# EEGAmp_Thruhole.net
KiCad netlist of a schematic drawn in EAGLE
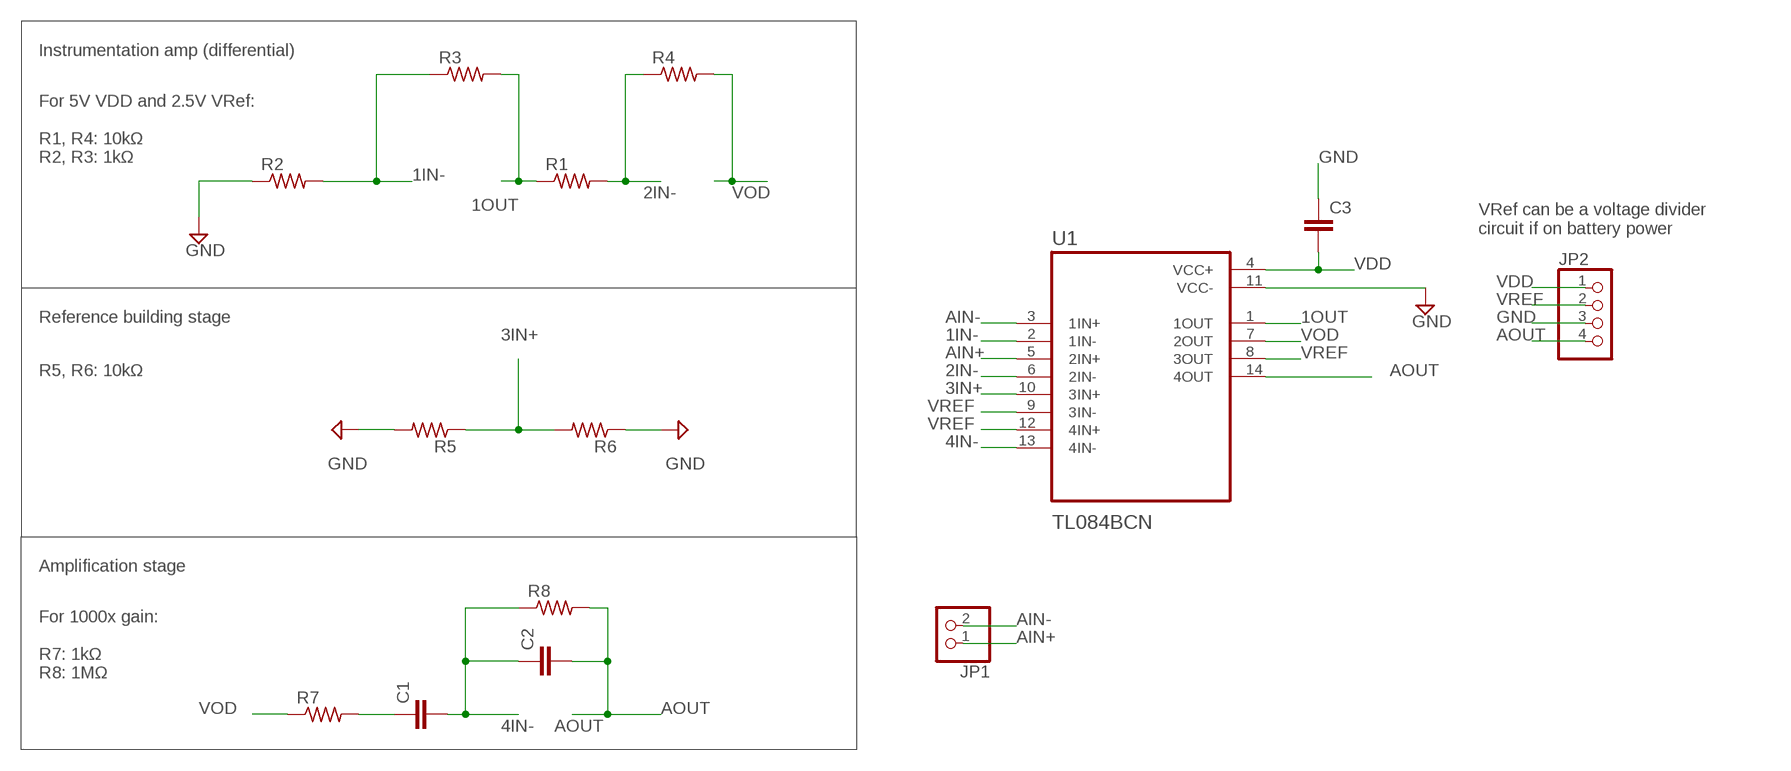
[diagram p0: schematic, sheet 1]

(export (version "E")
  (design (tool "Eeschema 10.0.6"))
  (components
    (comp (ref "C1")
      (value "C2.5/2")
      (footprint "eagle-import:C2.5-2")
      (libsource (lib "eagle-import") (part "C2.5/2"))
    )
    (comp (ref "C2")
      (value "C2.5/2")
      (footprint "eagle-import:C2.5-2")
      (libsource (lib "eagle-import") (part "C2.5/2"))
    )
    (comp (ref "C3")
      (value "C2.5/2")
      (footprint "eagle-import:C2.5-2")
      (libsource (lib "eagle-import") (part "C2.5/2"))
    )
    (comp (ref "JP1")
      (value "PINHD-1X2")
      (footprint "eagle-import:1X02")
      (libsource (lib "eagle-import") (part "PINHD-1X2"))
    )
    (comp (ref "JP2")
      (value "PINHD-1X4")
      (footprint "eagle-import:1X04")
      (libsource (lib "eagle-import") (part "PINHD-1X4"))
    )
    (comp (ref "R1")
      (value "R-US_0204/5")
      (footprint "eagle-import:0204_5")
      (libsource (lib "eagle-import") (part "R-US_0204/5"))
    )
    (comp (ref "R2")
      (value "R-US_0204/5")
      (footprint "eagle-import:0204_5")
      (libsource (lib "eagle-import") (part "R-US_0204/5"))
    )
    (comp (ref "R3")
      (value "R-US_0204/5")
      (footprint "eagle-import:0204_5")
      (libsource (lib "eagle-import") (part "R-US_0204/5"))
    )
    (comp (ref "R4")
      (value "R-US_0204/5")
      (footprint "eagle-import:0204_5")
      (libsource (lib "eagle-import") (part "R-US_0204/5"))
    )
    (comp (ref "R5")
      (value "R-US_0204/5")
      (footprint "eagle-import:0204_5")
      (libsource (lib "eagle-import") (part "R-US_0204/5"))
    )
    (comp (ref "R6")
      (value "R-US_0204/5")
      (footprint "eagle-import:0204_5")
      (libsource (lib "eagle-import") (part "R-US_0204/5"))
    )
    (comp (ref "R7")
      (value "R-US_0204/5")
      (footprint "eagle-import:0204_5")
      (libsource (lib "eagle-import") (part "R-US_0204/5"))
    )
    (comp (ref "R8")
      (value "R-US_0204/5")
      (footprint "eagle-import:0204_5")
      (libsource (lib "eagle-import") (part "R-US_0204/5"))
    )
    (comp (ref "U1")
      (value "TL084BCN")
      (footprint "eagle-import:DIP794W45P254L1969H508Q14")
      (fields (field (name "MF") "Texas Instruments"))
      (libsource (lib "eagle-import") (part "TL084BCN"))
    )
  )
  (nets
    (net (code "1") (name "/1IN-") (class "Default")
      (node (ref "R2") (pin "2") (pinfunction "2_2") (pintype "passive"))
      (node (ref "R3") (pin "1") (pinfunction "1_1") (pintype "passive"))
      (node (ref "U1") (pin "2") (pinfunction "1IN-_2") (pintype "input"))
    )
    (net (code "2") (name "/1OUT") (class "Default")
      (node (ref "R1") (pin "1") (pinfunction "1_1") (pintype "passive"))
      (node (ref "R3") (pin "2") (pinfunction "2_2") (pintype "passive"))
      (node (ref "U1") (pin "1") (pinfunction "1OUT_1") (pintype "output"))
    )
    (net (code "3") (name "/2IN-") (class "Default")
      (node (ref "R1") (pin "2") (pinfunction "2_2") (pintype "passive"))
      (node (ref "R4") (pin "1") (pinfunction "1_1") (pintype "passive"))
      (node (ref "U1") (pin "6") (pinfunction "2IN-_6") (pintype "input"))
    )
    (net (code "4") (name "/3IN+") (class "Default")
      (node (ref "R5") (pin "1") (pinfunction "1_1") (pintype "passive"))
      (node (ref "R6") (pin "2") (pinfunction "2_2") (pintype "passive"))
      (node (ref "U1") (pin "10") (pinfunction "3IN+_10") (pintype "input"))
    )
    (net (code "5") (name "/4IN-") (class "Default")
      (node (ref "C1") (pin "2") (pinfunction "2_2") (pintype "passive"))
      (node (ref "C2") (pin "1") (pinfunction "1_1") (pintype "passive"))
      (node (ref "R8") (pin "1") (pinfunction "1_1") (pintype "passive"))
      (node (ref "U1") (pin "13") (pinfunction "4IN-_13") (pintype "input"))
    )
    (net (code "6") (name "/AIN+") (class "Default")
      (node (ref "JP1") (pin "1") (pinfunction "1_1") (pintype "passive"))
      (node (ref "U1") (pin "5") (pinfunction "2IN+_5") (pintype "input"))
    )
    (net (code "7") (name "/AIN-") (class "Default")
      (node (ref "JP1") (pin "2") (pinfunction "2_2") (pintype "passive"))
      (node (ref "U1") (pin "3") (pinfunction "1IN+_3") (pintype "input"))
    )
    (net (code "8") (name "/AOUT") (class "Default")
      (node (ref "C2") (pin "2") (pinfunction "2_2") (pintype "passive"))
      (node (ref "JP2") (pin "4") (pinfunction "4_4") (pintype "passive"))
      (node (ref "R8") (pin "2") (pinfunction "2_2") (pintype "passive"))
      (node (ref "U1") (pin "14") (pinfunction "4OUT_14") (pintype "output"))
    )
    (net (code "9") (name "/VDD") (class "Default")
      (node (ref "C3") (pin "2") (pinfunction "2_2") (pintype "passive"))
      (node (ref "JP2") (pin "1") (pinfunction "1_1") (pintype "passive"))
      (node (ref "U1") (pin "4") (pinfunction "VCC+_4") (pintype "power_in"))
    )
    (net (code "10") (name "/VOD") (class "Default")
      (node (ref "R4") (pin "2") (pinfunction "2_2") (pintype "passive"))
      (node (ref "R7") (pin "1") (pinfunction "1_1") (pintype "passive"))
      (node (ref "U1") (pin "7") (pinfunction "2OUT_7") (pintype "output"))
    )
    (net (code "11") (name "/VREF") (class "Default")
      (node (ref "JP2") (pin "2") (pinfunction "2_2") (pintype "passive"))
      (node (ref "U1") (pin "12") (pinfunction "4IN+_12") (pintype "input"))
      (node (ref "U1") (pin "8") (pinfunction "3OUT_8") (pintype "output"))
      (node (ref "U1") (pin "9") (pinfunction "3IN-_9") (pintype "input"))
    )
    (net (code "12") (name "GND") (class "Default")
      (node (ref "C3") (pin "1") (pinfunction "1_1") (pintype "passive"))
      (node (ref "JP2") (pin "3") (pinfunction "3_3") (pintype "passive"))
      (node (ref "R2") (pin "1") (pinfunction "1_1") (pintype "passive"))
      (node (ref "R5") (pin "2") (pinfunction "2_2") (pintype "passive"))
      (node (ref "R6") (pin "1") (pinfunction "1_1") (pintype "passive"))
      (node (ref "U1") (pin "11") (pinfunction "VCC-_11") (pintype "power_in"))
    )
    (net (code "13") (name "Net-(C1-Pad1)") (class "Default")
      (node (ref "C1") (pin "1") (pinfunction "1_1") (pintype "passive"))
      (node (ref "R7") (pin "2") (pinfunction "2_2") (pintype "passive"))
    )
  )
)
